# connector.net
KiCad netlist of a schematic drawn in Altium Designer
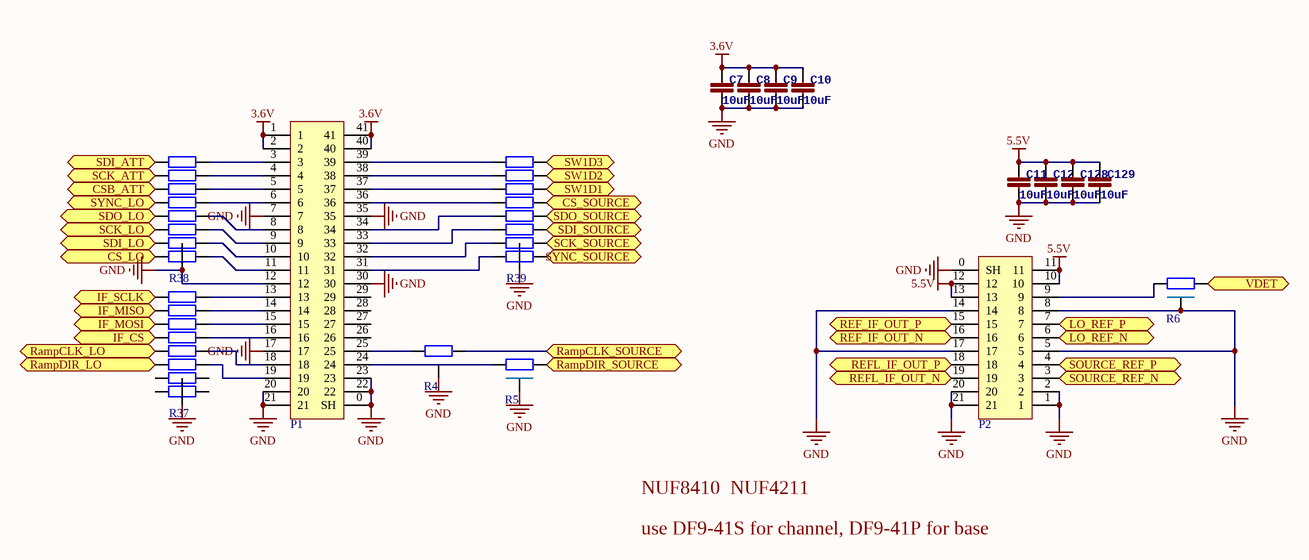
[diagram p0: connector.SchDoc]

(export (version "E")
  (design (tool "Eeschema 10.0.6"))
  (components
    (comp (ref "C7")
      (value "10uF")
      (footprint "0603L")
      (description "<b>Capacitor</b>\nStandard 0603 ceramic capacitor, and 0.1\" leaded capacitor.")
      (fields (field (name "PARTNO") "CC0402ZRY5V7BB104"))
      (libsource (lib "pixhawk2") (part "CAP0402-CAP"))
    )
    (comp (ref "C8")
      (value "10uF")
      (footprint "0603L")
      (description "<b>Capacitor</b>\nStandard 0603 ceramic capacitor, and 0.1\" leaded capacitor.")
      (fields (field (name "PARTNO") "CC0402ZRY5V7BB104"))
      (libsource (lib "pixhawk2") (part "CAP0402-CAP"))
    )
    (comp (ref "C9")
      (value "10uF")
      (footprint "0603L")
      (description "<b>Capacitor</b>\nStandard 0603 ceramic capacitor, and 0.1\" leaded capacitor.")
      (fields (field (name "PARTNO") "CC0402ZRY5V7BB104"))
      (libsource (lib "pixhawk2") (part "CAP0402-CAP"))
    )
    (comp (ref "C10")
      (value "10uF")
      (footprint "0603L")
      (description "<b>Capacitor</b>\nStandard 0603 ceramic capacitor, and 0.1\" leaded capacitor.")
      (fields (field (name "PARTNO") "CC0402ZRY5V7BB104"))
      (libsource (lib "pixhawk2") (part "CAP0402-CAP"))
    )
    (comp (ref "C11")
      (value "10uF")
      (footprint "0603L")
      (description "<b>Capacitor</b>\nStandard 0603 ceramic capacitor, and 0.1\" leaded capacitor.")
      (fields (field (name "PARTNO") "CC0402ZRY5V7BB104"))
      (libsource (lib "pixhawk2") (part "CAP0402-CAP"))
    )
    (comp (ref "C12")
      (value "10uF")
      (footprint "0603L")
      (description "<b>Capacitor</b>\nStandard 0603 ceramic capacitor, and 0.1\" leaded capacitor.")
      (fields (field (name "PARTNO") "CC0402ZRY5V7BB104"))
      (libsource (lib "pixhawk2") (part "CAP0402-CAP"))
    )
    (comp (ref "C128")
      (value "10uF")
      (footprint "0603L")
      (description "<b>Capacitor</b>\nStandard 0603 ceramic capacitor, and 0.1\" leaded capacitor.")
      (fields (field (name "PARTNO") "CC0402ZRY5V7BB104"))
      (libsource (lib "pixhawk2") (part "CAP0402-CAP"))
    )
    (comp (ref "C129")
      (value "10uF")
      (footprint "0603L")
      (description "<b>Capacitor</b>\nStandard 0603 ceramic capacitor, and 0.1\" leaded capacitor.")
      (fields (field (name "PARTNO") "CC0402ZRY5V7BB104"))
      (libsource (lib "pixhawk2") (part "CAP0402-CAP"))
    )
    (comp (ref "P1") (value "DF9-41S") (footprint "DF9-41S") (libsource (lib "cyusb3014") (part "DF9-41S")))
    (comp (ref "P2") (value "DF9-21") (footprint "DF9-21S") (libsource (lib "cyusb3014") (part "DF9-21")))
    (comp (ref "R4") (value "PiFilter") (footprint "PiFIiter") (libsource (lib "F4SDR") (part "PiFilter")))
    (comp (ref "R5") (value "PiFilter") (footprint "PiFIiter") (libsource (lib "") (part "PiFilter_1")))
    (comp (ref "R6") (value "PiFilter") (footprint "PiFIiter") (libsource (lib "F4SDR") (part "PiFilter")))
    (comp (ref "R37") (value "NUF8xxx") (footprint "NUF8xxx") (libsource (lib "F4SDR") (part "NUF8xxx")))
    (comp (ref "R38") (value "NUF8xxx") (footprint "NUF8xxx") (libsource (lib "F4SDR") (part "NUF8xxx")))
    (comp (ref "R39") (value "NUF8xxx") (footprint "NUF8xxx") (libsource (lib "F4SDR") (part "NUF8xxx")))
  )
  (nets
    (net (code "1") (name "/CSB_ATT") (class "Default")
      (node (ref "R38") (pin "3") (pinfunction "3_3") (pintype "passive"))
    )
    (net (code "2") (name "/CS_LO") (class "Default")
      (node (ref "R38") (pin "8") (pinfunction "8_8") (pintype "passive"))
    )
    (net (code "3") (name "/CS_SOURCE") (class "Default")
      (node (ref "R39") (pin "13") (pinfunction "13_13") (pintype "passive"))
    )
    (net (code "4") (name "/IF_CS") (class "Default")
      (node (ref "R37") (pin "4") (pinfunction "4_4") (pintype "passive"))
    )
    (net (code "5") (name "/IF_MISO") (class "Default")
      (node (ref "R37") (pin "2") (pinfunction "2_2") (pintype "passive"))
    )
    (net (code "6") (name "/IF_MOSI") (class "Default")
      (node (ref "R37") (pin "3") (pinfunction "3_3") (pintype "passive"))
    )
    (net (code "7") (name "/IF_SCLK") (class "Default")
      (node (ref "R37") (pin "1") (pinfunction "1_1") (pintype "passive"))
    )
    (net (code "8") (name "/LO_REF_N") (class "Default")
      (node (ref "P2") (pin "6") (pinfunction "6_6") (pintype "passive"))
    )
    (net (code "9") (name "/LO_REF_P") (class "Default")
      (node (ref "P2") (pin "7") (pinfunction "7_7") (pintype "passive"))
    )
    (net (code "10") (name "/REFL_IF_OUT_N") (class "Default")
      (node (ref "P2") (pin "19") (pinfunction "19_19") (pintype "passive"))
    )
    (net (code "11") (name "/REFL_IF_OUT_P") (class "Default")
      (node (ref "P2") (pin "18") (pinfunction "18_18") (pintype "passive"))
    )
    (net (code "12") (name "/REF_IF_OUT_N") (class "Default")
      (node (ref "P2") (pin "16") (pinfunction "16_16") (pintype "passive"))
    )
    (net (code "13") (name "/REF_IF_OUT_P") (class "Default")
      (node (ref "P2") (pin "15") (pinfunction "15_15") (pintype "passive"))
    )
    (net (code "14") (name "/RampCLK_LO") (class "Default")
      (node (ref "R37") (pin "5") (pinfunction "5_5") (pintype "passive"))
    )
    (net (code "15") (name "/RampCLK_SOURCE") (class "Default")
      (node (ref "R4") (pin "1") (pinfunction "1_1") (pintype "passive"))
    )
    (net (code "16") (name "/RampDIR_LO") (class "Default")
      (node (ref "R37") (pin "6") (pinfunction "6_6") (pintype "passive"))
    )
    (net (code "17") (name "/RampDIR_SOURCE") (class "Default")
      (node (ref "R5") (pin "2") (pinfunction "2_2") (pintype "passive"))
    )
    (net (code "18") (name "/SCK_ATT") (class "Default")
      (node (ref "R38") (pin "2") (pinfunction "2_2") (pintype "passive"))
    )
    (net (code "19") (name "/SCK_LO") (class "Default")
      (node (ref "R38") (pin "6") (pinfunction "6_6") (pintype "passive"))
    )
    (net (code "20") (name "/SCK_SOURCE") (class "Default")
      (node (ref "R39") (pin "10") (pinfunction "10_10") (pintype "passive"))
    )
    (net (code "21") (name "/SDI_ATT") (class "Default")
      (node (ref "R38") (pin "1") (pinfunction "1_1") (pintype "passive"))
    )
    (net (code "22") (name "/SDI_LO") (class "Default")
      (node (ref "R38") (pin "7") (pinfunction "7_7") (pintype "passive"))
    )
    (net (code "23") (name "/SDI_SOURCE") (class "Default")
      (node (ref "R39") (pin "11") (pinfunction "11_11") (pintype "passive"))
    )
    (net (code "24") (name "/SDO_LO") (class "Default")
      (node (ref "R38") (pin "5") (pinfunction "5_5") (pintype "passive"))
    )
    (net (code "25") (name "/SDO_SOURCE") (class "Default")
      (node (ref "R39") (pin "12") (pinfunction "12_12") (pintype "passive"))
    )
    (net (code "26") (name "/SOURCE_REF_N") (class "Default")
      (node (ref "P2") (pin "3") (pinfunction "3_3") (pintype "passive"))
    )
    (net (code "27") (name "/SOURCE_REF_P") (class "Default")
      (node (ref "P2") (pin "4") (pinfunction "4_4") (pintype "passive"))
    )
    (net (code "28") (name "/SW1D1") (class "Default")
      (node (ref "R39") (pin "14") (pinfunction "14_14") (pintype "passive"))
    )
    (net (code "29") (name "/SW1D2") (class "Default")
      (node (ref "R39") (pin "15") (pinfunction "15_15") (pintype "passive"))
    )
    (net (code "30") (name "/SW1D3") (class "Default")
      (node (ref "R39") (pin "16") (pinfunction "16_16") (pintype "passive"))
    )
    (net (code "31") (name "/SYNC_LO") (class "Default")
      (node (ref "R38") (pin "4") (pinfunction "4_4") (pintype "passive"))
    )
    (net (code "32") (name "/SYNC_SOURCE") (class "Default")
      (node (ref "R39") (pin "9") (pinfunction "9_9") (pintype "passive"))
    )
    (net (code "33") (name "/VDET") (class "Default")
      (node (ref "R6") (pin "1") (pinfunction "1_1") (pintype "passive"))
    )
    (net (code "34") (name "3.6V") (class "Default")
      (node (ref "C10") (pin "2") (pinfunction "2_2") (pintype "passive"))
      (node (ref "C7") (pin "2") (pinfunction "2_2") (pintype "passive"))
      (node (ref "C8") (pin "2") (pinfunction "2_2") (pintype "passive"))
      (node (ref "C9") (pin "2") (pinfunction "2_2") (pintype "passive"))
      (node (ref "P1") (pin "1") (pinfunction "1_1") (pintype "passive"))
      (node (ref "P1") (pin "2") (pinfunction "2_2") (pintype "passive"))
      (node (ref "P1") (pin "40") (pinfunction "40_40") (pintype "passive"))
      (node (ref "P1") (pin "41") (pinfunction "41_41") (pintype "passive"))
    )
    (net (code "35") (name "5.5V") (class "Default")
      (node (ref "C11") (pin "2") (pinfunction "2_2") (pintype "passive"))
      (node (ref "C12") (pin "2") (pinfunction "2_2") (pintype "passive"))
      (node (ref "C128") (pin "2") (pinfunction "2_2") (pintype "passive"))
      (node (ref "C129") (pin "2") (pinfunction "2_2") (pintype "passive"))
      (node (ref "P2") (pin "10") (pinfunction "10_10") (pintype "passive"))
      (node (ref "P2") (pin "11") (pinfunction "11_11") (pintype "passive"))
      (node (ref "P2") (pin "12") (pinfunction "12_12") (pintype "passive"))
      (node (ref "P2") (pin "13") (pinfunction "13_13") (pintype "passive"))
    )
    (net (code "36") (name "GND") (class "Default")
      (node (ref "C10") (pin "1") (pinfunction "1_1") (pintype "passive"))
      (node (ref "C11") (pin "1") (pinfunction "1_1") (pintype "passive"))
      (node (ref "C12") (pin "1") (pinfunction "1_1") (pintype "passive"))
      (node (ref "C128") (pin "1") (pinfunction "1_1") (pintype "passive"))
      (node (ref "C129") (pin "1") (pinfunction "1_1") (pintype "passive"))
      (node (ref "C7") (pin "1") (pinfunction "1_1") (pintype "passive"))
      (node (ref "C8") (pin "1") (pinfunction "1_1") (pintype "passive"))
      (node (ref "C9") (pin "1") (pinfunction "1_1") (pintype "passive"))
      (node (ref "P1") (pin "0") (pinfunction "SH_0") (pintype "passive"))
      (node (ref "P1") (pin "12") (pinfunction "12_12") (pintype "passive"))
      (node (ref "P1") (pin "17") (pinfunction "17_17") (pintype "passive"))
      (node (ref "P1") (pin "20") (pinfunction "20_20") (pintype "passive"))
      (node (ref "P1") (pin "21") (pinfunction "21_21") (pintype "passive"))
      (node (ref "P1") (pin "22") (pinfunction "22_22") (pintype "passive"))
      (node (ref "P1") (pin "23") (pinfunction "23_23") (pintype "passive"))
      (node (ref "P1") (pin "30") (pinfunction "30_30") (pintype "passive"))
      (node (ref "P1") (pin "35") (pinfunction "35_35") (pintype "passive"))
      (node (ref "P1") (pin "7") (pinfunction "7_7") (pintype "passive"))
      (node (ref "P2") (pin "0") (pinfunction "SH_0") (pintype "passive"))
      (node (ref "P2") (pin "1") (pinfunction "1_1") (pintype "passive"))
      (node (ref "P2") (pin "14") (pinfunction "14_14") (pintype "passive"))
      (node (ref "P2") (pin "17") (pinfunction "17_17") (pintype "passive"))
      (node (ref "P2") (pin "2") (pinfunction "2_2") (pintype "passive"))
      (node (ref "P2") (pin "20") (pinfunction "20_20") (pintype "passive"))
      (node (ref "P2") (pin "21") (pinfunction "21_21") (pintype "passive"))
      (node (ref "P2") (pin "5") (pinfunction "5_5") (pintype "passive"))
      (node (ref "P2") (pin "8") (pinfunction "8_8") (pintype "passive"))
      (node (ref "R37") (pin "0") (pinfunction "0_0") (pintype "passive"))
      (node (ref "R38") (pin "0") (pinfunction "0_0") (pintype "passive"))
      (node (ref "R39") (pin "0") (pinfunction "0_0") (pintype "passive"))
      (node (ref "R4") (pin "3") (pinfunction "3_3") (pintype "passive"))
      (node (ref "R5") (pin "3") (pinfunction "3_3") (pintype "passive"))
      (node (ref "R6") (pin "3") (pinfunction "3_3") (pintype "passive"))
    )
    (net (code "37") (name "Net-(P1-Pad3)") (class "Default")
      (node (ref "P1") (pin "3") (pinfunction "3_3") (pintype "passive"))
      (node (ref "R38") (pin "16") (pinfunction "16_16") (pintype "passive"))
    )
    (net (code "38") (name "Net-(P1-Pad4)") (class "Default")
      (node (ref "P1") (pin "4") (pinfunction "4_4") (pintype "passive"))
      (node (ref "R38") (pin "15") (pinfunction "15_15") (pintype "passive"))
    )
    (net (code "39") (name "Net-(P1-Pad5)") (class "Default")
      (node (ref "P1") (pin "5") (pinfunction "5_5") (pintype "passive"))
      (node (ref "R38") (pin "14") (pinfunction "14_14") (pintype "passive"))
    )
    (net (code "40") (name "Net-(P1-Pad6)") (class "Default")
      (node (ref "P1") (pin "6") (pinfunction "6_6") (pintype "passive"))
      (node (ref "R38") (pin "13") (pinfunction "13_13") (pintype "passive"))
    )
    (net (code "41") (name "Net-(P1-Pad8)") (class "Default")
      (node (ref "P1") (pin "8") (pinfunction "8_8") (pintype "passive"))
      (node (ref "R38") (pin "12") (pinfunction "12_12") (pintype "passive"))
    )
    (net (code "42") (name "Net-(P1-Pad9)") (class "Default")
      (node (ref "P1") (pin "9") (pinfunction "9_9") (pintype "passive"))
      (node (ref "R38") (pin "11") (pinfunction "11_11") (pintype "passive"))
    )
    (net (code "43") (name "Net-(P1-Pad10)") (class "Default")
      (node (ref "P1") (pin "10") (pinfunction "10_10") (pintype "passive"))
      (node (ref "R38") (pin "10") (pinfunction "10_10") (pintype "passive"))
    )
    (net (code "44") (name "Net-(P1-Pad11)") (class "Default")
      (node (ref "P1") (pin "11") (pinfunction "11_11") (pintype "passive"))
      (node (ref "R38") (pin "9") (pinfunction "9_9") (pintype "passive"))
    )
    (net (code "45") (name "Net-(P1-Pad13)") (class "Default")
      (node (ref "P1") (pin "13") (pinfunction "13_13") (pintype "passive"))
      (node (ref "R37") (pin "16") (pinfunction "16_16") (pintype "passive"))
    )
    (net (code "46") (name "Net-(P1-Pad14)") (class "Default")
      (node (ref "P1") (pin "14") (pinfunction "14_14") (pintype "passive"))
      (node (ref "R37") (pin "15") (pinfunction "15_15") (pintype "passive"))
    )
    (net (code "47") (name "Net-(P1-Pad15)") (class "Default")
      (node (ref "P1") (pin "15") (pinfunction "15_15") (pintype "passive"))
      (node (ref "R37") (pin "14") (pinfunction "14_14") (pintype "passive"))
    )
    (net (code "48") (name "Net-(P1-Pad16)") (class "Default")
      (node (ref "P1") (pin "16") (pinfunction "16_16") (pintype "passive"))
      (node (ref "R37") (pin "13") (pinfunction "13_13") (pintype "passive"))
    )
    (net (code "49") (name "Net-(P1-Pad18)") (class "Default")
      (node (ref "P1") (pin "18") (pinfunction "18_18") (pintype "passive"))
      (node (ref "R37") (pin "12") (pinfunction "12_12") (pintype "passive"))
    )
    (net (code "50") (name "Net-(P1-Pad19)") (class "Default")
      (node (ref "P1") (pin "19") (pinfunction "19_19") (pintype "passive"))
      (node (ref "R37") (pin "11") (pinfunction "11_11") (pintype "passive"))
    )
    (net (code "51") (name "Net-(P1-Pad24)") (class "Default")
      (node (ref "P1") (pin "24") (pinfunction "24_24") (pintype "passive"))
      (node (ref "R5") (pin "1") (pinfunction "1_1") (pintype "passive"))
    )
    (net (code "52") (name "Net-(P1-Pad25)") (class "Default")
      (node (ref "P1") (pin "25") (pinfunction "25_25") (pintype "passive"))
      (node (ref "R4") (pin "2") (pinfunction "2_2") (pintype "passive"))
    )
    (net (code "53") (name "Net-(P1-Pad31)") (class "Default")
      (node (ref "P1") (pin "31") (pinfunction "31_31") (pintype "passive"))
      (node (ref "R39") (pin "8") (pinfunction "8_8") (pintype "passive"))
    )
    (net (code "54") (name "Net-(P1-Pad32)") (class "Default")
      (node (ref "P1") (pin "32") (pinfunction "32_32") (pintype "passive"))
      (node (ref "R39") (pin "7") (pinfunction "7_7") (pintype "passive"))
    )
    (net (code "55") (name "Net-(P1-Pad33)") (class "Default")
      (node (ref "P1") (pin "33") (pinfunction "33_33") (pintype "passive"))
      (node (ref "R39") (pin "6") (pinfunction "6_6") (pintype "passive"))
    )
    (net (code "56") (name "Net-(P1-Pad34)") (class "Default")
      (node (ref "P1") (pin "34") (pinfunction "34_34") (pintype "passive"))
      (node (ref "R39") (pin "5") (pinfunction "5_5") (pintype "passive"))
    )
    (net (code "57") (name "Net-(P1-Pad36)") (class "Default")
      (node (ref "P1") (pin "36") (pinfunction "36_36") (pintype "passive"))
      (node (ref "R39") (pin "4") (pinfunction "4_4") (pintype "passive"))
    )
    (net (code "58") (name "Net-(P1-Pad37)") (class "Default")
      (node (ref "P1") (pin "37") (pinfunction "37_37") (pintype "passive"))
      (node (ref "R39") (pin "3") (pinfunction "3_3") (pintype "passive"))
    )
    (net (code "59") (name "Net-(P1-Pad38)") (class "Default")
      (node (ref "P1") (pin "38") (pinfunction "38_38") (pintype "passive"))
      (node (ref "R39") (pin "2") (pinfunction "2_2") (pintype "passive"))
    )
    (net (code "60") (name "Net-(P1-Pad39)") (class "Default")
      (node (ref "P1") (pin "39") (pinfunction "39_39") (pintype "passive"))
      (node (ref "R39") (pin "1") (pinfunction "1_1") (pintype "passive"))
    )
    (net (code "61") (name "Net-(P2-Pad9)") (class "Default")
      (node (ref "P2") (pin "9") (pinfunction "9_9") (pintype "passive"))
      (node (ref "R6") (pin "2") (pinfunction "2_2") (pintype "passive"))
    )
    (net (code "62") (name "unconnected-(P1-Pad26)") (class "Default")
      (node (ref "P1") (pin "26") (pinfunction "26_26") (pintype "passive"))
    )
    (net (code "63") (name "unconnected-(P1-Pad27)") (class "Default")
      (node (ref "P1") (pin "27") (pinfunction "27_27") (pintype "passive"))
    )
    (net (code "64") (name "unconnected-(P1-Pad28)") (class "Default")
      (node (ref "P1") (pin "28") (pinfunction "28_28") (pintype "passive"))
    )
    (net (code "65") (name "unconnected-(P1-Pad29)") (class "Default")
      (node (ref "P1") (pin "29") (pinfunction "29_29") (pintype "passive"))
    )
    (net (code "66") (name "unconnected-(R37-Pad7)") (class "Default")
      (node (ref "R37") (pin "7") (pinfunction "7_7") (pintype "passive"))
    )
    (net (code "67") (name "unconnected-(R37-Pad8)") (class "Default")
      (node (ref "R37") (pin "8") (pinfunction "8_8") (pintype "passive"))
    )
    (net (code "68") (name "unconnected-(R37-Pad9)") (class "Default")
      (node (ref "R37") (pin "9") (pinfunction "9_9") (pintype "passive"))
    )
    (net (code "69") (name "unconnected-(R37-Pad10)") (class "Default")
      (node (ref "R37") (pin "10") (pinfunction "10_10") (pintype "passive"))
    )
  )
)
